# 2_-_Communication.net
KiCad netlist of a schematic drawn in Altium Designer
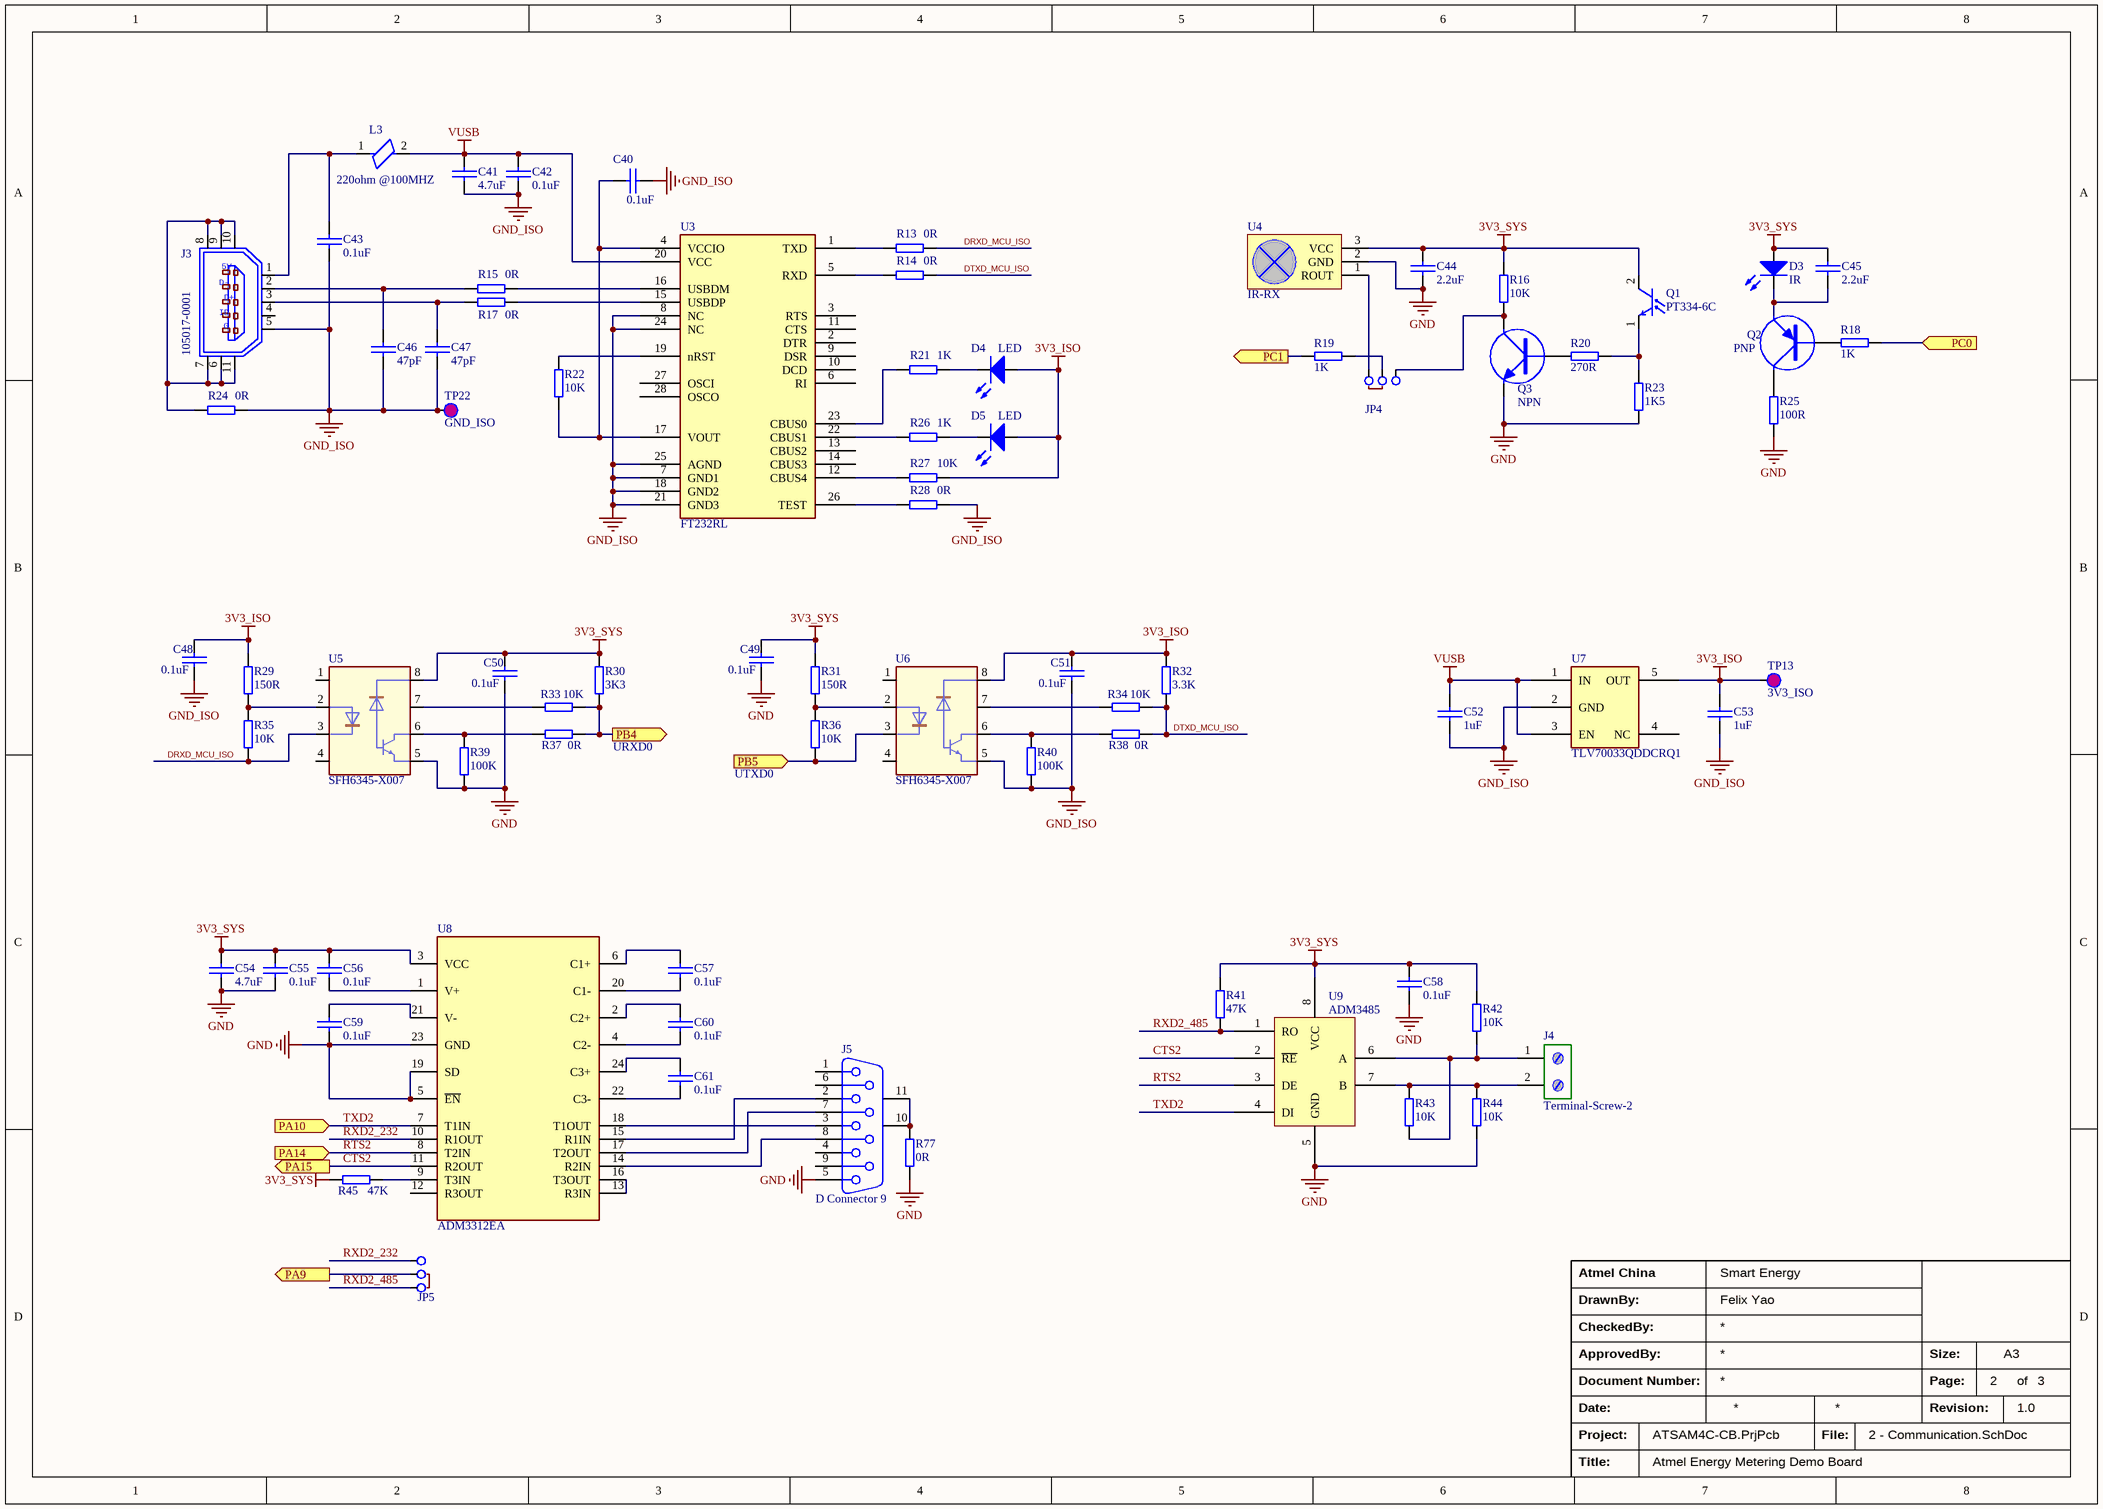
[diagram p0: 2 - Communication.SchDoc]

(export (version "E")
  (design (tool "Eeschema 10.0.6"))
  (components
    (comp (ref "C40") (value "0.1uF") (footprint "C0603") (libsource (lib "SchLib(AD10)") (part "CAP")))
    (comp (ref "C41") (value "4.7uF") (footprint "C0805") (libsource (lib "SchLib(AD10)") (part "CAP")))
    (comp (ref "C42") (value "0.1uF") (footprint "C0603") (libsource (lib "SchLib(AD10)") (part "CAP")))
    (comp (ref "C43") (value "0.1uF") (footprint "C0603") (libsource (lib "SchLib(AD10)") (part "CAP")))
    (comp (ref "C44") (value "2.2uF") (footprint "C0805") (libsource (lib "SchLib(AD10)") (part "CAP")))
    (comp (ref "C45") (value "2.2uF") (footprint "C0805") (libsource (lib "SchLib(AD10)") (part "CAP")))
    (comp (ref "C46") (value "47pF") (footprint "C0603") (libsource (lib "SchLib(AD10)") (part "CAP")))
    (comp (ref "C47") (value "47pF") (footprint "C0603") (libsource (lib "SchLib(AD10)") (part "CAP")))
    (comp (ref "C48") (value "0.1uF") (footprint "C0603") (libsource (lib "SchLib(AD10)") (part "CAP")))
    (comp (ref "C49") (value "0.1uF") (footprint "C0603") (libsource (lib "SchLib(AD10)") (part "CAP")))
    (comp (ref "C50") (value "0.1uF") (footprint "C0603") (libsource (lib "SchLib(AD10)") (part "CAP")))
    (comp (ref "C51") (value "0.1uF") (footprint "C0603") (libsource (lib "SchLib(AD10)") (part "CAP")))
    (comp (ref "C52") (value "1uF") (footprint "C0805") (libsource (lib "SchLib(AD10)") (part "CAP")))
    (comp (ref "C53") (value "1uF") (footprint "C0805") (libsource (lib "SchLib(AD10)") (part "CAP")))
    (comp (ref "C54") (value "4.7uF") (footprint "C0805") (libsource (lib "SchLib(AD10)") (part "CAP")))
    (comp (ref "C55") (value "0.1uF") (footprint "C0603") (libsource (lib "SchLib(AD10)") (part "CAP")))
    (comp (ref "C56") (value "0.1uF") (footprint "C0603") (libsource (lib "SchLib(AD10)") (part "CAP")))
    (comp (ref "C57") (value "0.1uF") (footprint "C0603") (libsource (lib "SchLib(AD10)") (part "CAP")))
    (comp (ref "C58") (value "0.1uF") (footprint "C0603") (libsource (lib "SchLib(AD10)") (part "CAP")))
    (comp (ref "C59") (value "0.1uF") (footprint "C0603") (libsource (lib "SchLib(AD10)") (part "CAP")))
    (comp (ref "C60") (value "0.1uF") (footprint "C0603") (libsource (lib "SchLib(AD10)") (part "CAP")))
    (comp (ref "C61") (value "0.1uF") (footprint "C0603") (libsource (lib "SchLib(AD10)") (part "CAP")))
    (comp (ref "D3") (value "IR") (footprint "LED-5mm") (libsource (lib "SchLib(AD10)") (part "LED")))
    (comp (ref "D4") (value "LED") (footprint "LED-0805") (libsource (lib "SchLib(AD10)") (part "LED")))
    (comp (ref "D5") (value "LED") (footprint "LED-0805") (libsource (lib "SchLib(AD10)") (part "LED")))
    (comp (ref "J3")
      (value "105017-0001")
      (footprint "micro_usb_dip_b")
      (description "MicroUSB B port,5 Position,Right Angle,Gold Flash 1u")
      (fields (field (name "MANUFACTURER") "Molex"))
      (libsource (lib "SchLib(AD10)") (part "1981584-1_0"))
    )
    (comp (ref "J4")
      (value "Terminal-Screw-2")
      (footprint "TE-1776119-2")
      (libsource (lib "SchLib(AD10)") (part "Terminal-Screw-2"))
    )
    (comp (ref "J5")
      (value "D Connector 9")
      (footprint "DSUB1.385-2H9")
      (description "Receptacle Assembly, 9 Position, Right Angle")
      (fields (field (name "PUBLISHER") "Altium Limited"))
      (libsource (lib "SchLib(AD10)") (part "D Connector 9"))
    )
    (comp (ref "JP4") (value "JMP3") (footprint "JMP3") (libsource (lib "SchLib(AD10)") (part "JMP3")))
    (comp (ref "JP5") (value "JMP3") (footprint "JMP3") (libsource (lib "SchLib(AD10)") (part "JMP3")))
    (comp (ref "L3")
      (value "220ohm @100MHZ")
      (footprint "0805")
      (description "Ferrite Bead,470OHM@100MHz,+/-25%,  200mA,")
      (fields
        (field (name "MANUFACTURER") "Murata")
        (field (name "MANUFACTURER PART NUMBER") "BLM21BD471SN1")
      )
      (libsource (lib "SchLib(AD10)") (part "BEAD_ FERRITE"))
    )
    (comp (ref "Q1")
      (value "PT334-6C")
      (footprint "LED-DIP-100")
      (description "PT334-6C；EVERLIGHT;")
      (fields (field (name "MANUFACTURER") "Everlight"))
      (libsource (lib "SchLib(AD10)") (part "QSB363CZR_0"))
    )
    (comp (ref "Q2") (value "PNP") (footprint "SOT-23") (libsource (lib "SchLib(AD10)") (part "PNP")))
    (comp (ref "Q3") (value "NPN") (footprint "SOT-23") (libsource (lib "SchLib(AD10)") (part "NPN")))
    (comp (ref "R13") (value "0R") (footprint "R0603") (libsource (lib "SchLib(AD10)") (part "RES")))
    (comp (ref "R14") (value "0R") (footprint "R0603") (libsource (lib "SchLib(AD10)") (part "RES")))
    (comp (ref "R15") (value "0R") (footprint "R0603") (libsource (lib "SchLib(AD10)") (part "RES")))
    (comp (ref "R16") (value "10K") (footprint "R0603") (libsource (lib "SchLib(AD10)") (part "RES")))
    (comp (ref "R17") (value "0R") (footprint "R0603") (libsource (lib "SchLib(AD10)") (part "RES")))
    (comp (ref "R18") (value "1K") (footprint "R0603") (libsource (lib "SchLib(AD10)") (part "RES")))
    (comp (ref "R19") (value "1K") (footprint "R0603") (libsource (lib "SchLib(AD10)") (part "RES")))
    (comp (ref "R20") (value "270R") (footprint "R0603") (libsource (lib "SchLib(AD10)") (part "RES")))
    (comp (ref "R21") (value "1K") (footprint "R0603") (libsource (lib "SchLib(AD10)") (part "RES")))
    (comp (ref "R22") (value "10K") (footprint "R0603") (libsource (lib "SchLib(AD10)") (part "RES")))
    (comp (ref "R23") (value "1K5") (footprint "R0603") (libsource (lib "SchLib(AD10)") (part "RES")))
    (comp (ref "R24") (value "0R") (footprint "R0603") (libsource (lib "SchLib(AD10)") (part "RES")))
    (comp (ref "R25") (value "100R") (footprint "R0603") (libsource (lib "SchLib(AD10)") (part "RES")))
    (comp (ref "R26") (value "1K") (footprint "R0603") (libsource (lib "SchLib(AD10)") (part "RES")))
    (comp (ref "R27") (value "10K") (footprint "R0603") (libsource (lib "SchLib(AD10)") (part "RES")))
    (comp (ref "R28") (value "0R") (footprint "R0603") (libsource (lib "SchLib(AD10)") (part "RES")))
    (comp (ref "R29") (value "150R") (footprint "R0603") (libsource (lib "SchLib(AD10)") (part "RES")))
    (comp (ref "R30") (value "3K3") (footprint "R0603") (libsource (lib "SchLib(AD10)") (part "RES")))
    (comp (ref "R31") (value "150R") (footprint "R0603") (libsource (lib "SchLib(AD10)") (part "RES")))
    (comp (ref "R32") (value "3.3K") (footprint "R0603") (libsource (lib "SchLib(AD10)") (part "RES")))
    (comp (ref "R33") (value "10K") (footprint "R0603") (libsource (lib "SchLib(AD10)") (part "RES")))
    (comp (ref "R34") (value "10K") (footprint "R0603") (libsource (lib "SchLib(AD10)") (part "RES")))
    (comp (ref "R35") (value "10K") (footprint "R0603") (libsource (lib "SchLib(AD10)") (part "RES")))
    (comp (ref "R36") (value "10K") (footprint "R0603") (libsource (lib "SchLib(AD10)") (part "RES")))
    (comp (ref "R37") (value "0R") (footprint "R0603") (libsource (lib "SchLib(AD10)") (part "RES")))
    (comp (ref "R38") (value "0R") (footprint "R0603") (libsource (lib "SchLib(AD10)") (part "RES")))
    (comp (ref "R39") (value "100K") (footprint "R0603") (libsource (lib "SchLib(AD10)") (part "RES")))
    (comp (ref "R40") (value "100K") (footprint "R0603") (libsource (lib "SchLib(AD10)") (part "RES")))
    (comp (ref "R41") (value "47K") (footprint "R0603") (libsource (lib "SchLib(AD10)") (part "RES")))
    (comp (ref "R42") (value "10K") (footprint "R0603") (libsource (lib "SchLib(AD10)") (part "RES")))
    (comp (ref "R43") (value "10K") (footprint "R0603") (libsource (lib "SchLib(AD10)") (part "RES")))
    (comp (ref "R44") (value "10K") (footprint "R0603") (libsource (lib "SchLib(AD10)") (part "RES")))
    (comp (ref "R45") (value "47K") (footprint "R0603") (libsource (lib "SchLib(AD10)") (part "RES")))
    (comp (ref "R77") (value "0R") (footprint "R0603") (libsource (lib "SchLib(AD10)") (part "RES")))
    (comp (ref "TP13")
      (value "3V3_ISO")
      (footprint "TP")
      (libsource (lib "SchLib(AD10)") (part "TEST-POINT"))
    )
    (comp (ref "TP22")
      (value "GND_ISO")
      (footprint "TP")
      (libsource (lib "SchLib(AD10)") (part "TEST-POINT"))
    )
    (comp (ref "U3")
      (value "FT232RL")
      (footprint "SSOP-28")
      (description "IC,USB to serial UART interface")
      (fields (field (name "MANUFACTURER") "FTDI") (field (name "MANUFACTURER PART NUMBER") "FT232RL-REEL"))
      (libsource (lib "SchLib(AD10)") (part "FT232RL_2"))
    )
    (comp (ref "U4") (value "IR-RX") (footprint "IR-Rx") (libsource (lib "SchLib(AD10)") (part "IR-RX")))
    (comp (ref "U5")
      (value "SFH6345-X007")
      (footprint "SO08-400")
      (description "IC,High Speed Optocoupler 1Mbd 15kV/μs CMR Transistor Output")
      (fields (field (name "MANUFACTURER") "Vishay"))
      (libsource (lib "SchLib(AD10)") (part "SFH6345-X007"))
    )
    (comp (ref "U6")
      (value "SFH6345-X007")
      (footprint "SO08-400")
      (description "IC,High Speed Optocoupler 1Mbd 15kV/μs CMR Transistor Output")
      (fields (field (name "MANUFACTURER") "Vishay"))
      (libsource (lib "SchLib(AD10)") (part "SFH6345-X007"))
    )
    (comp (ref "U7")
      (value "TLV70033QDDCRQ1")
      (footprint "SOT23-5")
      (description "IC,200-mA  Low-IQ Low-Dropout Regulator")
      (fields (field (name "MANUFACTURER") "TI") (field (name "MANUFACTURER PART NUMBER") "TLV70033QDDCR"))
      (libsource (lib "SchLib(AD10)") (part "TLV70033"))
    )
    (comp (ref "U8")
      (value "ADM3312EA")
      (footprint "TSSOP-24")
      (libsource (lib "SchLib(AD10)") (part "ADM3312EA"))
    )
    (comp (ref "U9")
      (value "ADM3485")
      (footprint "SOP-8")
      (description "TI3485")
      (libsource (lib "SchLib(AD10)") (part "TI3485"))
    )
  )
  (nets
    (net (code "1") (name "/CTS2") (class "Default")
      (node (ref "U8") (pin "11") (pinfunction "R2OUT_11") (pintype "passive"))
      (node (ref "U9") (pin "2") (pinfunction "~{RE}_2") (pintype "passive"))
    )
    (net (code "2") (name "/DRXD_MCU_ISO") (class "Default")
      (node (ref "R13") (pin "2") (pinfunction "2_2") (pintype "passive"))
      (node (ref "R35") (pin "1") (pinfunction "1_1") (pintype "passive"))
      (node (ref "U5") (pin "3") (pinfunction "3_3") (pintype "passive"))
    )
    (net (code "3") (name "/DTXD_MCU_ISO") (class "Default")
      (node (ref "R14") (pin "2") (pinfunction "2_2") (pintype "passive"))
      (node (ref "R32") (pin "1") (pinfunction "1_1") (pintype "passive"))
      (node (ref "R34") (pin "1") (pinfunction "1_1") (pintype "passive"))
      (node (ref "R38") (pin "1") (pinfunction "1_1") (pintype "passive"))
    )
    (net (code "4") (name "/PA9") (class "Default")
      (node (ref "JP5") (pin "2") (pinfunction "2_2") (pintype "passive"))
    )
    (net (code "5") (name "/PB4") (class "Default")
      (node (ref "R30") (pin "1") (pinfunction "1_1") (pintype "passive"))
      (node (ref "R33") (pin "1") (pinfunction "1_1") (pintype "passive"))
      (node (ref "R37") (pin "1") (pinfunction "1_1") (pintype "passive"))
    )
    (net (code "6") (name "/PB5") (class "Default")
      (node (ref "R36") (pin "1") (pinfunction "1_1") (pintype "passive"))
      (node (ref "U6") (pin "3") (pinfunction "3_3") (pintype "passive"))
    )
    (net (code "7") (name "/PC0") (class "Default")
      (node (ref "R18") (pin "1") (pinfunction "1_1") (pintype "passive"))
    )
    (net (code "8") (name "/PC1") (class "Default")
      (node (ref "R19") (pin "1") (pinfunction "1_1") (pintype "passive"))
    )
    (net (code "9") (name "/RTS2") (class "Default")
      (node (ref "U8") (pin "8") (pinfunction "T2IN_8") (pintype "passive"))
      (node (ref "U9") (pin "3") (pinfunction "DE_3") (pintype "passive"))
    )
    (net (code "10") (name "/RXD2_232") (class "Default")
      (node (ref "JP5") (pin "3") (pinfunction "3_3") (pintype "passive"))
      (node (ref "U8") (pin "10") (pinfunction "R1OUT_10") (pintype "passive"))
    )
    (net (code "11") (name "/RXD2_485") (class "Default")
      (node (ref "JP5") (pin "1") (pinfunction "1_1") (pintype "passive"))
      (node (ref "R41") (pin "2") (pinfunction "2_2") (pintype "passive"))
      (node (ref "U9") (pin "1") (pinfunction "RO_1") (pintype "passive"))
    )
    (net (code "12") (name "/TXD2") (class "Default")
      (node (ref "U8") (pin "7") (pinfunction "T1IN_7") (pintype "passive"))
      (node (ref "U9") (pin "4") (pinfunction "DI_4") (pintype "passive"))
    )
    (net (code "13") (name "3V3_ISO") (class "Default")
      (node (ref "C48") (pin "2") (pintype "passive"))
      (node (ref "C51") (pin "2") (pintype "passive"))
      (node (ref "C53") (pin "2") (pintype "passive"))
      (node (ref "D4") (pin "A") (pinfunction "A_A") (pintype "passive"))
      (node (ref "D5") (pin "A") (pinfunction "A_A") (pintype "passive"))
      (node (ref "R27") (pin "2") (pinfunction "2_2") (pintype "passive"))
      (node (ref "R29") (pin "2") (pinfunction "2_2") (pintype "passive"))
      (node (ref "R32") (pin "2") (pinfunction "2_2") (pintype "passive"))
      (node (ref "TP13") (pin "1") (pinfunction "1_1") (pintype "passive"))
      (node (ref "U6") (pin "8") (pinfunction "8_8") (pintype "passive"))
      (node (ref "U7") (pin "5") (pinfunction "OUT_5") (pintype "passive"))
    )
    (net (code "14") (name "3V3_SYS") (class "Default")
      (node (ref "C44") (pin "2") (pintype "passive"))
      (node (ref "C45") (pin "2") (pintype "passive"))
      (node (ref "C49") (pin "2") (pintype "passive"))
      (node (ref "C50") (pin "2") (pintype "passive"))
      (node (ref "C54") (pin "2") (pintype "passive"))
      (node (ref "C55") (pin "1") (pintype "passive"))
      (node (ref "C56") (pin "2") (pintype "passive"))
      (node (ref "C58") (pin "1") (pintype "passive"))
      (node (ref "D3") (pin "A") (pinfunction "A_A") (pintype "passive"))
      (node (ref "Q1") (pin "2") (pinfunction "C_2") (pintype "passive"))
      (node (ref "R16") (pin "2") (pinfunction "2_2") (pintype "passive"))
      (node (ref "R30") (pin "2") (pinfunction "2_2") (pintype "passive"))
      (node (ref "R31") (pin "2") (pinfunction "2_2") (pintype "passive"))
      (node (ref "R41") (pin "1") (pinfunction "1_1") (pintype "passive"))
      (node (ref "R42") (pin "2") (pinfunction "2_2") (pintype "passive"))
      (node (ref "R45") (pin "2") (pinfunction "2_2") (pintype "passive"))
      (node (ref "U4") (pin "3") (pinfunction "VCC_3") (pintype "passive"))
      (node (ref "U5") (pin "8") (pinfunction "8_8") (pintype "passive"))
      (node (ref "U8") (pin "3") (pinfunction "VCC_3") (pintype "passive"))
      (node (ref "U9") (pin "8") (pinfunction "VCC_8") (pintype "passive"))
    )
    (net (code "15") (name "GND") (class "Default")
      (node (ref "C44") (pin "1") (pintype "passive"))
      (node (ref "C49") (pin "1") (pintype "passive"))
      (node (ref "C50") (pin "1") (pintype "passive"))
      (node (ref "C54") (pin "1") (pintype "passive"))
      (node (ref "C55") (pin "2") (pintype "passive"))
      (node (ref "C58") (pin "2") (pintype "passive"))
      (node (ref "C59") (pin "1") (pintype "passive"))
      (node (ref "J5") (pin "5") (pinfunction "5_5") (pintype "passive"))
      (node (ref "Q3") (pin "2") (pinfunction "E_2") (pintype "passive"))
      (node (ref "R23") (pin "1") (pinfunction "1_1") (pintype "passive"))
      (node (ref "R25") (pin "1") (pinfunction "1_1") (pintype "passive"))
      (node (ref "R39") (pin "1") (pinfunction "1_1") (pintype "passive"))
      (node (ref "R44") (pin "1") (pinfunction "1_1") (pintype "passive"))
      (node (ref "R77") (pin "1") (pinfunction "1_1") (pintype "passive"))
      (node (ref "U4") (pin "2") (pinfunction "GND_2") (pintype "passive"))
      (node (ref "U5") (pin "5") (pinfunction "5_5") (pintype "passive"))
      (node (ref "U8") (pin "19") (pinfunction "SD_19") (pintype "passive"))
      (node (ref "U8") (pin "23") (pinfunction "GND_23") (pintype "passive"))
      (node (ref "U8") (pin "5") (pinfunction "~{EN}_5") (pintype "passive"))
      (node (ref "U9") (pin "5") (pinfunction "GND_5") (pintype "passive"))
    )
    (net (code "16") (name "GND_ISO") (class "Default")
      (node (ref "C40") (pin "1") (pintype "passive"))
      (node (ref "C41") (pin "1") (pintype "passive"))
      (node (ref "C42") (pin "1") (pintype "passive"))
      (node (ref "C43") (pin "1") (pintype "passive"))
      (node (ref "C46") (pin "1") (pintype "passive"))
      (node (ref "C47") (pin "1") (pintype "passive"))
      (node (ref "C48") (pin "1") (pintype "passive"))
      (node (ref "C51") (pin "1") (pintype "passive"))
      (node (ref "C52") (pin "1") (pintype "passive"))
      (node (ref "C53") (pin "1") (pintype "passive"))
      (node (ref "J3") (pin "5") (pinfunction "5_5") (pintype "passive"))
      (node (ref "R24") (pin "2") (pinfunction "2_2") (pintype "passive"))
      (node (ref "R28") (pin "2") (pinfunction "2_2") (pintype "passive"))
      (node (ref "R40") (pin "1") (pinfunction "1_1") (pintype "passive"))
      (node (ref "TP22") (pin "1") (pinfunction "1_1") (pintype "passive"))
      (node (ref "U3") (pin "18") (pinfunction "GND2_18") (pintype "power_in"))
      (node (ref "U3") (pin "21") (pinfunction "GND3_21") (pintype "power_in"))
      (node (ref "U3") (pin "24") (pinfunction "NC_24") (pintype "power_in"))
      (node (ref "U3") (pin "25") (pinfunction "AGND_25") (pintype "power_in"))
      (node (ref "U3") (pin "7") (pinfunction "GND1_7") (pintype "power_in"))
      (node (ref "U3") (pin "8") (pinfunction "NC_8") (pintype "power_in"))
      (node (ref "U6") (pin "5") (pinfunction "5_5") (pintype "passive"))
      (node (ref "U7") (pin "2") (pinfunction "GND_2") (pintype "power_in"))
    )
    (net (code "17") (name "Net-(C43-Pad2)") (class "Default")
      (node (ref "C43") (pin "2") (pintype "passive"))
      (node (ref "J3") (pin "1") (pinfunction "1_1") (pintype "passive"))
      (node (ref "L3") (pin "1") (pinfunction "1_1") (pintype "passive"))
    )
    (net (code "18") (name "Net-(C46-Pad2)") (class "Default")
      (node (ref "C46") (pin "2") (pintype "passive"))
      (node (ref "J3") (pin "2") (pinfunction "2_2") (pintype "passive"))
      (node (ref "R15") (pin "1") (pinfunction "1_1") (pintype "passive"))
    )
    (net (code "19") (name "Net-(C47-Pad2)") (class "Default")
      (node (ref "C47") (pin "2") (pintype "passive"))
      (node (ref "J3") (pin "3") (pinfunction "3_3") (pintype "passive"))
      (node (ref "R17") (pin "1") (pinfunction "1_1") (pintype "passive"))
    )
    (net (code "20") (name "Net-(D4-PadK)") (class "Default")
      (node (ref "D4") (pin "K") (pinfunction "K_K") (pintype "passive"))
      (node (ref "R21") (pin "2") (pinfunction "2_2") (pintype "passive"))
    )
    (net (code "21") (name "Net-(D5-PadK)") (class "Default")
      (node (ref "D5") (pin "K") (pinfunction "K_K") (pintype "passive"))
      (node (ref "R26") (pin "2") (pinfunction "2_2") (pintype "passive"))
    )
    (net (code "22") (name "Net-(J3-Pad10)") (class "Default")
      (node (ref "J3") (pin "10") (pinfunction "10_10") (pintype "passive"))
      (node (ref "J3") (pin "11") (pinfunction "11_11") (pintype "passive"))
      (node (ref "J3") (pin "6") (pinfunction "6_6") (pintype "passive"))
      (node (ref "J3") (pin "7") (pinfunction "7_7") (pintype "passive"))
      (node (ref "J3") (pin "8") (pinfunction "8_8") (pintype "passive"))
      (node (ref "J3") (pin "9") (pinfunction "9_9") (pintype "passive"))
      (node (ref "R24") (pin "1") (pinfunction "1_1") (pintype "passive"))
    )
    (net (code "23") (name "Net-(J5-MH1)") (class "Default")
      (node (ref "J5") (pin "10") (pinfunction "MH1_10") (pintype "passive"))
      (node (ref "J5") (pin "11") (pinfunction "MH2_11") (pintype "passive"))
      (node (ref "R77") (pin "2") (pinfunction "2_2") (pintype "passive"))
    )
    (net (code "24") (name "Net-(JP4-Pad2)") (class "Default")
      (node (ref "JP4") (pin "2") (pinfunction "2_2") (pintype "passive"))
      (node (ref "R19") (pin "2") (pinfunction "2_2") (pintype "passive"))
    )
    (net (code "25") (name "Net-(Q1-E)") (class "Default")
      (node (ref "Q1") (pin "1") (pinfunction "E_1") (pintype "passive"))
      (node (ref "R20") (pin "2") (pinfunction "2_2") (pintype "passive"))
      (node (ref "R23") (pin "2") (pinfunction "2_2") (pintype "passive"))
    )
    (net (code "26") (name "Net-(Q2-B)") (class "Default")
      (node (ref "Q2") (pin "1") (pinfunction "B_1") (pintype "passive"))
      (node (ref "R18") (pin "2") (pinfunction "2_2") (pintype "passive"))
    )
    (net (code "27") (name "Net-(Q2-C)") (class "Default")
      (node (ref "Q2") (pin "3") (pinfunction "C_3") (pintype "passive"))
      (node (ref "R25") (pin "2") (pinfunction "2_2") (pintype "passive"))
    )
    (net (code "28") (name "Net-(Q2-E)") (class "Default")
      (node (ref "C45") (pin "1") (pintype "passive"))
      (node (ref "D3") (pin "K") (pinfunction "K_K") (pintype "passive"))
      (node (ref "Q2") (pin "2") (pinfunction "E_2") (pintype "passive"))
    )
    (net (code "29") (name "Net-(Q3-B)") (class "Default")
      (node (ref "Q3") (pin "1") (pinfunction "B_1") (pintype "passive"))
      (node (ref "R20") (pin "1") (pinfunction "1_1") (pintype "passive"))
    )
    (net (code "30") (name "Net-(Q3-C)") (class "Default")
      (node (ref "JP4") (pin "3") (pinfunction "3_3") (pintype "passive"))
      (node (ref "Q3") (pin "3") (pinfunction "C_3") (pintype "passive"))
      (node (ref "R16") (pin "1") (pinfunction "1_1") (pintype "passive"))
    )
    (net (code "31") (name "Net-(R29-Pad1)") (class "Default")
      (node (ref "R29") (pin "1") (pinfunction "1_1") (pintype "passive"))
      (node (ref "R35") (pin "2") (pinfunction "2_2") (pintype "passive"))
      (node (ref "U5") (pin "2") (pinfunction "2_2") (pintype "passive"))
    )
    (net (code "32") (name "Net-(R31-Pad1)") (class "Default")
      (node (ref "R31") (pin "1") (pinfunction "1_1") (pintype "passive"))
      (node (ref "R36") (pin "2") (pinfunction "2_2") (pintype "passive"))
      (node (ref "U6") (pin "2") (pinfunction "2_2") (pintype "passive"))
    )
    (net (code "33") (name "Net-(R33-Pad2)") (class "Default")
      (node (ref "R33") (pin "2") (pinfunction "2_2") (pintype "passive"))
      (node (ref "U5") (pin "7") (pinfunction "7_7") (pintype "passive"))
    )
    (net (code "34") (name "Net-(R34-Pad2)") (class "Default")
      (node (ref "R34") (pin "2") (pinfunction "2_2") (pintype "passive"))
      (node (ref "U6") (pin "7") (pinfunction "7_7") (pintype "passive"))
    )
    (net (code "35") (name "Net-(R37-Pad2)") (class "Default")
      (node (ref "R37") (pin "2") (pinfunction "2_2") (pintype "passive"))
      (node (ref "R39") (pin "2") (pinfunction "2_2") (pintype "passive"))
      (node (ref "U5") (pin "6") (pinfunction "6_6") (pintype "passive"))
    )
    (net (code "36") (name "Net-(R38-Pad2)") (class "Default")
      (node (ref "R38") (pin "2") (pinfunction "2_2") (pintype "passive"))
      (node (ref "R40") (pin "2") (pinfunction "2_2") (pintype "passive"))
      (node (ref "U6") (pin "6") (pinfunction "6_6") (pintype "passive"))
    )
    (net (code "37") (name "Net-(U3-CBUS0)") (class "Default")
      (node (ref "R21") (pin "1") (pinfunction "1_1") (pintype "passive"))
      (node (ref "U3") (pin "23") (pinfunction "CBUS0_23") (pintype "passive"))
    )
    (net (code "38") (name "Net-(U3-CBUS1)") (class "Default")
      (node (ref "R26") (pin "1") (pinfunction "1_1") (pintype "passive"))
      (node (ref "U3") (pin "22") (pinfunction "CBUS1_22") (pintype "passive"))
    )
    (net (code "39") (name "Net-(U3-CBUS4)") (class "Default")
      (node (ref "R27") (pin "1") (pinfunction "1_1") (pintype "passive"))
      (node (ref "U3") (pin "12") (pinfunction "CBUS4_12") (pintype "passive"))
    )
    (net (code "40") (name "Net-(U3-RXD)") (class "Default")
      (node (ref "R14") (pin "1") (pinfunction "1_1") (pintype "passive"))
      (node (ref "U3") (pin "5") (pinfunction "RXD_5") (pintype "passive"))
    )
    (net (code "41") (name "Net-(U3-TEST)") (class "Default")
      (node (ref "R28") (pin "1") (pinfunction "1_1") (pintype "passive"))
      (node (ref "U3") (pin "26") (pinfunction "TEST_26") (pintype "passive"))
    )
    (net (code "42") (name "Net-(U3-TXD)") (class "Default")
      (node (ref "R13") (pin "1") (pinfunction "1_1") (pintype "passive"))
      (node (ref "U3") (pin "1") (pinfunction "TXD_1") (pintype "passive"))
    )
    (net (code "43") (name "Net-(U3-USBDM)") (class "Default")
      (node (ref "R15") (pin "2") (pinfunction "2_2") (pintype "passive"))
      (node (ref "U3") (pin "16") (pinfunction "USBDM_16") (pintype "passive"))
    )
    (net (code "44") (name "Net-(U3-USBDP)") (class "Default")
      (node (ref "R17") (pin "2") (pinfunction "2_2") (pintype "passive"))
      (node (ref "U3") (pin "15") (pinfunction "USBDP_15") (pintype "passive"))
    )
    (net (code "45") (name "Net-(U3-VCCIO)") (class "Default")
      (node (ref "C40") (pin "2") (pintype "passive"))
      (node (ref "R22") (pin "1") (pinfunction "1_1") (pintype "passive"))
      (node (ref "U3") (pin "17") (pinfunction "VOUT_17") (pintype "passive"))
      (node (ref "U3") (pin "4") (pinfunction "VCCIO_4") (pintype "power_in"))
    )
    (net (code "46") (name "Net-(U3-nRST)") (class "Default")
      (node (ref "R22") (pin "2") (pinfunction "2_2") (pintype "passive"))
      (node (ref "U3") (pin "19") (pinfunction "nRST_19") (pintype "passive"))
    )
    (net (code "47") (name "Net-(U4-ROUT)") (class "Default")
      (node (ref "JP4") (pin "1") (pinfunction "1_1") (pintype "passive"))
      (node (ref "U4") (pin "1") (pinfunction "ROUT_1") (pintype "passive"))
    )
    (net (code "48") (name "Net-(U8-C1+)") (class "Default")
      (node (ref "C57") (pin "2") (pintype "passive"))
      (node (ref "U8") (pin "6") (pinfunction "C1+_6") (pintype "passive"))
    )
    (net (code "49") (name "Net-(U8-C1-)") (class "Default")
      (node (ref "C57") (pin "1") (pintype "passive"))
      (node (ref "U8") (pin "20") (pinfunction "C1-_20") (pintype "passive"))
    )
    (net (code "50") (name "Net-(U8-C2+)") (class "Default")
      (node (ref "C60") (pin "2") (pintype "passive"))
      (node (ref "U8") (pin "2") (pinfunction "C2+_2") (pintype "passive"))
    )
    (net (code "51") (name "Net-(U8-C2-)") (class "Default")
      (node (ref "C60") (pin "1") (pintype "passive"))
      (node (ref "U8") (pin "4") (pinfunction "C2-_4") (pintype "passive"))
    )
    (net (code "52") (name "Net-(U8-C3+)") (class "Default")
      (node (ref "C61") (pin "2") (pintype "passive"))
      (node (ref "U8") (pin "24") (pinfunction "C3+_24") (pintype "passive"))
    )
    (net (code "53") (name "Net-(U8-C3-)") (class "Default")
      (node (ref "C61") (pin "1") (pintype "passive"))
      (node (ref "U8") (pin "22") (pinfunction "C3-_22") (pintype "passive"))
    )
    (net (code "54") (name "Net-(U8-R1IN)") (class "Default")
      (node (ref "J5") (pin "2") (pinfunction "2_2") (pintype "passive"))
      (node (ref "U8") (pin "15") (pinfunction "R1IN_15") (pintype "passive"))
    )
    (net (code "55") (name "Net-(U8-R2IN)") (class "Default")
      (node (ref "J5") (pin "8") (pinfunction "8_8") (pintype "passive"))
      (node (ref "U8") (pin "14") (pinfunction "R2IN_14") (pintype "passive"))
    )
    (net (code "56") (name "Net-(U8-R3IN)") (class "Default")
      (node (ref "U8") (pin "13") (pinfunction "R3IN_13") (pintype "passive"))
      (node (ref "U8") (pin "16") (pinfunction "T3OUT_16") (pintype "passive"))
    )
    (net (code "57") (name "Net-(U8-T1OUT)") (class "Default")
      (node (ref "J5") (pin "3") (pinfunction "3_3") (pintype "passive"))
      (node (ref "U8") (pin "18") (pinfunction "T1OUT_18") (pintype "passive"))
    )
    (net (code "58") (name "Net-(U8-T2OUT)") (class "Default")
      (node (ref "J5") (pin "7") (pinfunction "7_7") (pintype "passive"))
      (node (ref "U8") (pin "17") (pinfunction "T2OUT_17") (pintype "passive"))
    )
    (net (code "59") (name "Net-(U8-T3IN)") (class "Default")
      (node (ref "R45") (pin "1") (pinfunction "1_1") (pintype "passive"))
      (node (ref "U8") (pin "9") (pinfunction "T3IN_9") (pintype "passive"))
    )
    (net (code "60") (name "Net-(U8-V+)") (class "Default")
      (node (ref "C56") (pin "1") (pintype "passive"))
      (node (ref "U8") (pin "1") (pinfunction "V+_1") (pintype "passive"))
    )
    (net (code "61") (name "Net-(U8-V-)") (class "Default")
      (node (ref "C59") (pin "2") (pintype "passive"))
      (node (ref "U8") (pin "21") (pinfunction "V-_21") (pintype "passive"))
    )
    (net (code "62") (name "Net-(U9-A)") (class "Default")
      (node (ref "J4") (pin "1") (pinfunction "1_1") (pintype "passive"))
      (node (ref "R42") (pin "1") (pinfunction "1_1") (pintype "passive"))
      (node (ref "R43") (pin "1") (pinfunction "1_1") (pintype "passive"))
      (node (ref "U9") (pin "6") (pinfunction "A_6") (pintype "passive"))
    )
    (net (code "63") (name "Net-(U9-B)") (class "Default")
      (node (ref "J4") (pin "2") (pinfunction "2_2") (pintype "passive"))
      (node (ref "R43") (pin "2") (pinfunction "2_2") (pintype "passive"))
      (node (ref "R44") (pin "2") (pinfunction "2_2") (pintype "passive"))
      (node (ref "U9") (pin "7") (pinfunction "B_7") (pintype "passive"))
    )
    (net (code "64") (name "VUSB") (class "Default")
      (node (ref "C41") (pin "2") (pintype "passive"))
      (node (ref "C42") (pin "2") (pintype "passive"))
      (node (ref "C52") (pin "2") (pintype "passive"))
      (node (ref "L3") (pin "2") (pinfunction "2_2") (pintype "passive"))
      (node (ref "U3") (pin "20") (pinfunction "VCC_20") (pintype "power_in"))
      (node (ref "U7") (pin "1") (pinfunction "IN_1") (pintype "passive"))
      (node (ref "U7") (pin "3") (pinfunction "EN_3") (pintype "passive"))
    )
    (net (code "65") (name "unconnected-(J3-Pad4)") (class "Default")
      (node (ref "J3") (pin "4") (pinfunction "4_4") (pintype "passive"))
    )
    (net (code "66") (name "unconnected-(J5-Pad1)") (class "Default")
      (node (ref "J5") (pin "1") (pinfunction "1_1") (pintype "passive"))
    )
    (net (code "67") (name "unconnected-(J5-Pad4)") (class "Default")
      (node (ref "J5") (pin "4") (pinfunction "4_4") (pintype "passive"))
    )
    (net (code "68") (name "unconnected-(J5-Pad6)") (class "Default")
      (node (ref "J5") (pin "6") (pinfunction "6_6") (pintype "passive"))
    )
    (net (code "69") (name "unconnected-(J5-Pad9)") (class "Default")
      (node (ref "J5") (pin "9") (pinfunction "9_9") (pintype "passive"))
    )
    (net (code "70") (name "unconnected-(U3-CBUS2-Pad13)") (class "Default")
      (node (ref "U3") (pin "13") (pinfunction "CBUS2_13") (pintype "passive"))
    )
    (net (code "71") (name "unconnected-(U3-CBUS3-Pad14)") (class "Default")
      (node (ref "U3") (pin "14") (pinfunction "CBUS3_14") (pintype "passive"))
    )
    (net (code "72") (name "unconnected-(U3-CTS-Pad11)") (class "Default")
      (node (ref "U3") (pin "11") (pinfunction "CTS_11") (pintype "passive"))
    )
    (net (code "73") (name "unconnected-(U3-DCD-Pad10)") (class "Default")
      (node (ref "U3") (pin "10") (pinfunction "DCD_10") (pintype "passive"))
    )
    (net (code "74") (name "unconnected-(U3-DSR-Pad9)") (class "Default")
      (node (ref "U3") (pin "9") (pinfunction "DSR_9") (pintype "passive"))
    )
    (net (code "75") (name "unconnected-(U3-DTR-Pad2)") (class "Default")
      (node (ref "U3") (pin "2") (pinfunction "DTR_2") (pintype "passive"))
    )
    (net (code "76") (name "unconnected-(U3-OSCI-Pad27)") (class "Default")
      (node (ref "U3") (pin "27") (pinfunction "OSCI_27") (pintype "passive"))
    )
    (net (code "77") (name "unconnected-(U3-OSCO-Pad28)") (class "Default")
      (node (ref "U3") (pin "28") (pinfunction "OSCO_28") (pintype "passive"))
    )
    (net (code "78") (name "unconnected-(U3-RI-Pad6)") (class "Default")
      (node (ref "U3") (pin "6") (pinfunction "RI_6") (pintype "passive"))
    )
    (net (code "79") (name "unconnected-(U3-RTS-Pad3)") (class "Default")
      (node (ref "U3") (pin "3") (pinfunction "RTS_3") (pintype "passive"))
    )
    (net (code "80") (name "unconnected-(U5-Pad1)") (class "Default")
      (node (ref "U5") (pin "1") (pinfunction "1_1") (pintype "passive"))
    )
    (net (code "81") (name "unconnected-(U5-Pad4)") (class "Default")
      (node (ref "U5") (pin "4") (pinfunction "4_4") (pintype "passive"))
    )
    (net (code "82") (name "unconnected-(U6-Pad1)") (class "Default")
      (node (ref "U6") (pin "1") (pinfunction "1_1") (pintype "passive"))
    )
    (net (code "83") (name "unconnected-(U6-Pad4)") (class "Default")
      (node (ref "U6") (pin "4") (pinfunction "4_4") (pintype "passive"))
    )
    (net (code "84") (name "unconnected-(U7-NC-Pad4)") (class "Default")
      (node (ref "U7") (pin "4") (pinfunction "NC_4") (pintype "passive"))
    )
    (net (code "85") (name "unconnected-(U8-R3OUT-Pad12)") (class "Default")
      (node (ref "U8") (pin "12") (pinfunction "R3OUT_12") (pintype "passive"))
    )
  )
)
